# analog_in.net
KiCad netlist of a schematic drawn in Altium Designer
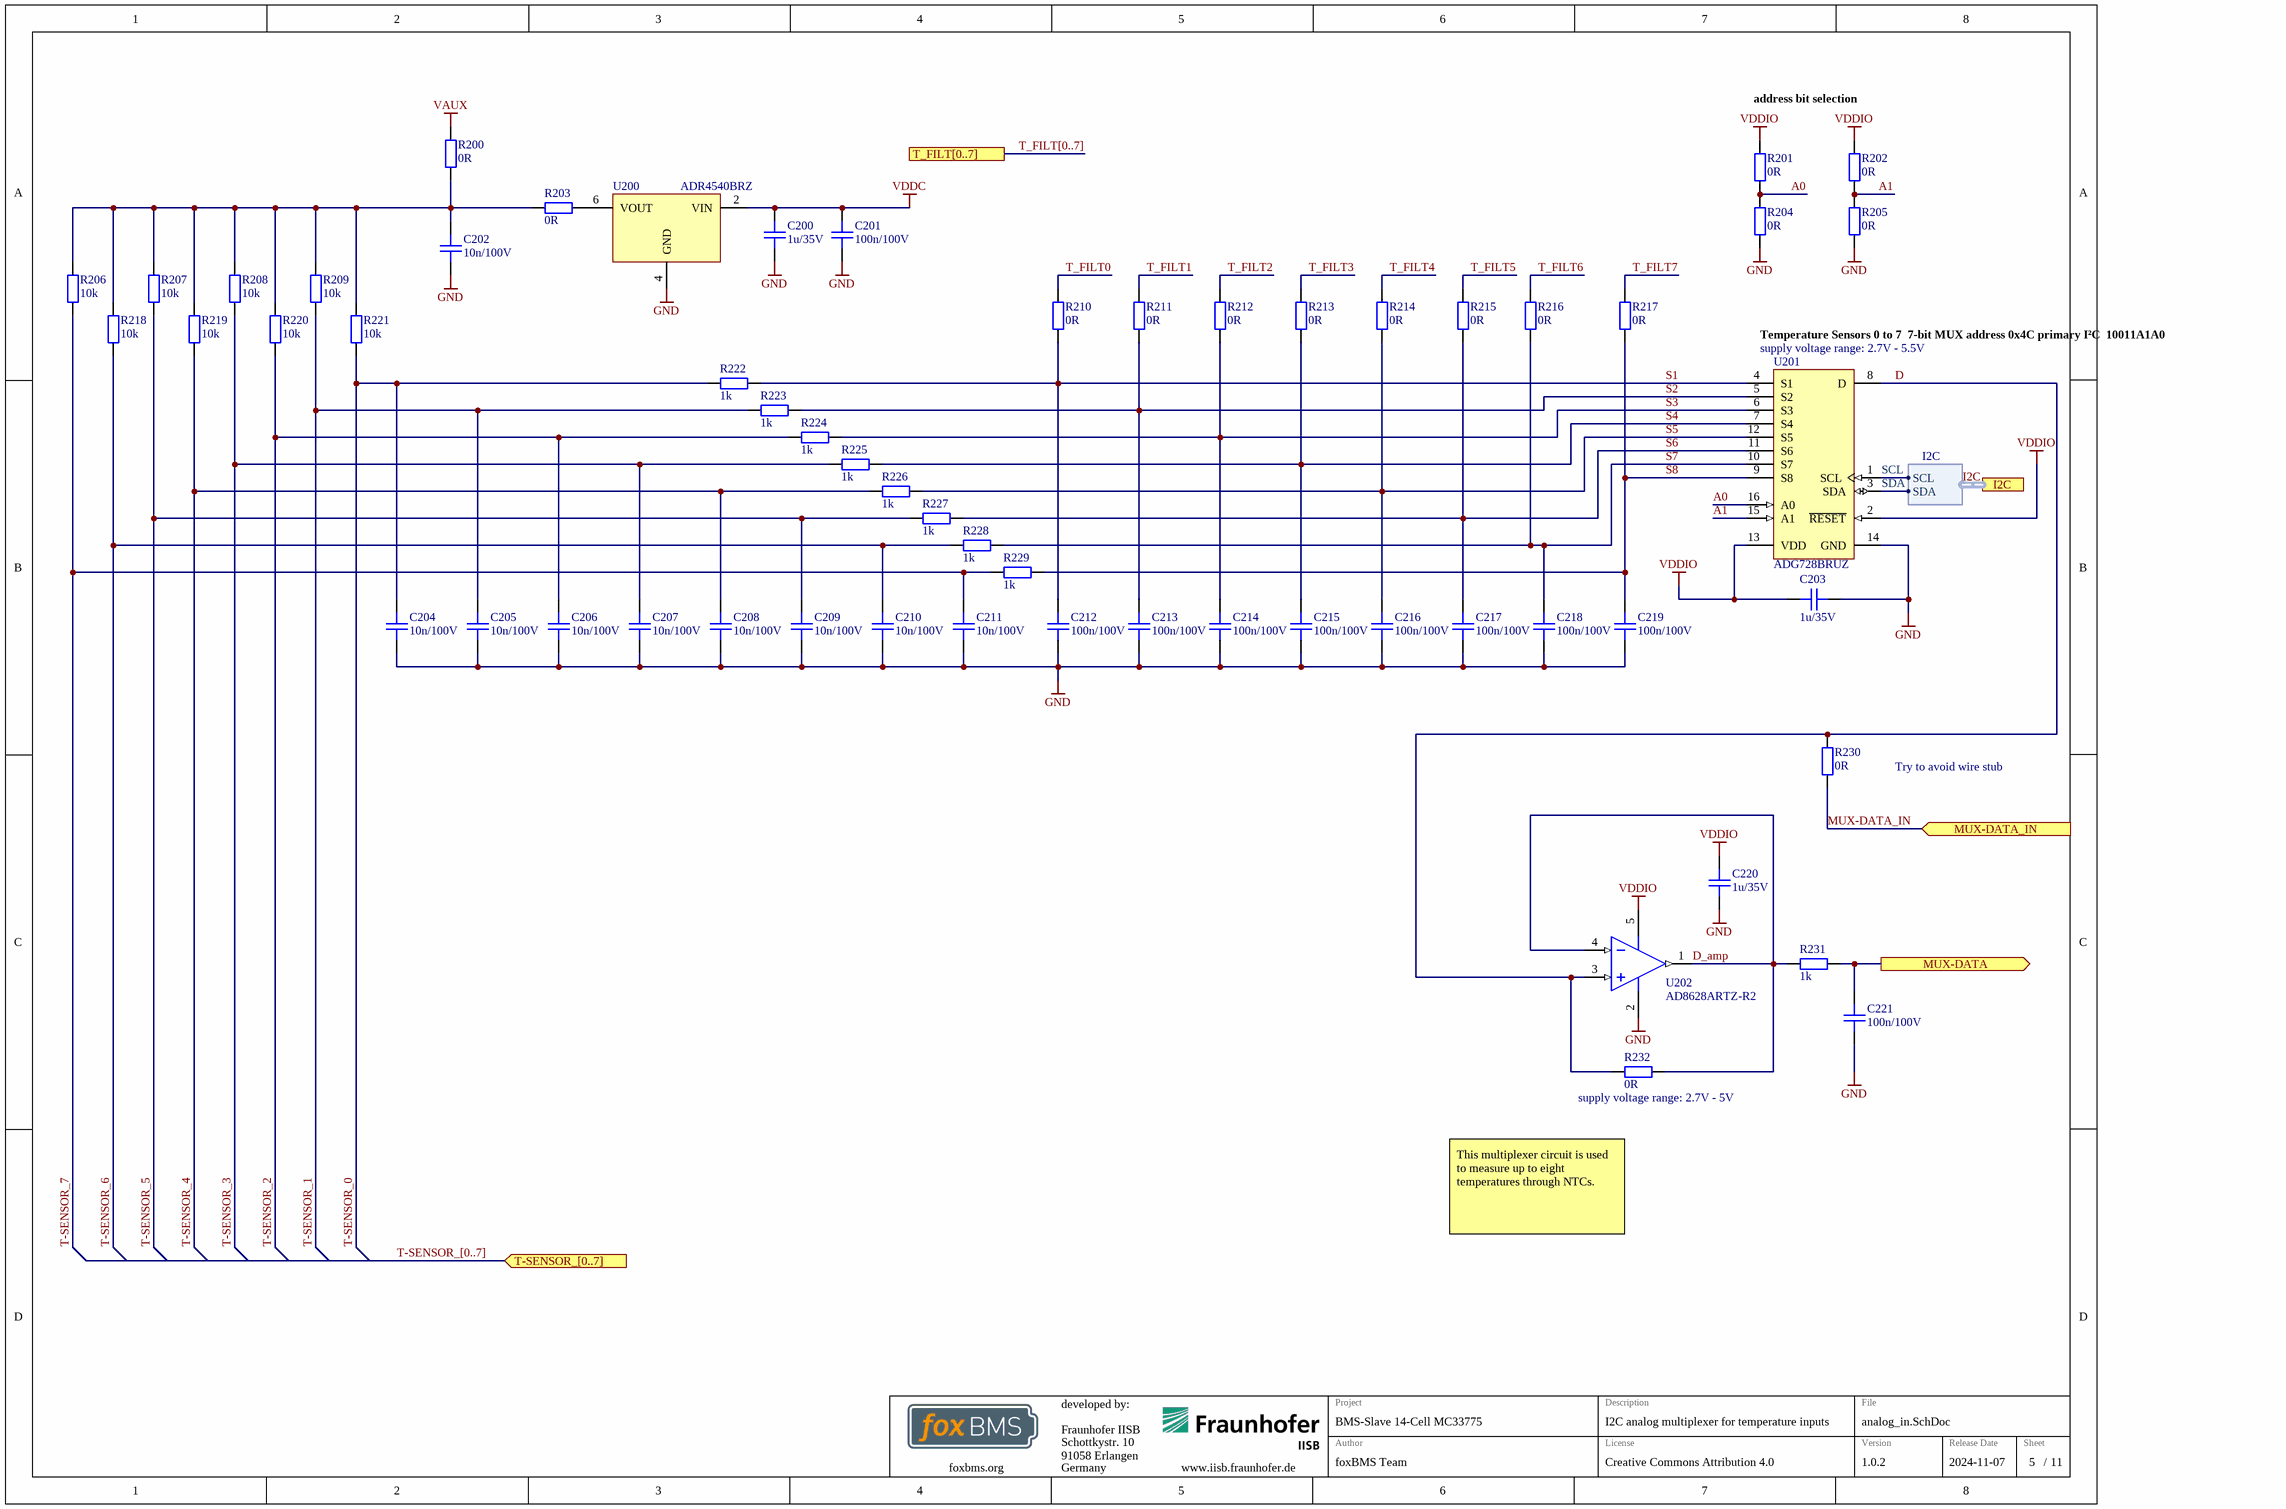
[diagram p0: analog_in.SchDoc]

(export (version "E")
  (design (tool "Eeschema 10.0.6"))
  (components
    (comp (ref "C200")
      (value "1u/35V")
      (footprint "CAPC1608X08N")
      (description "MLCC")
      (fields (field (name "PART NUMBER") "gen_C_ceramic_1u_35V_X7R_0603"))
      (libsource (lib "OE750") (part "C"))
    )
    (comp (ref "C201")
      (value "100n/100V")
      (footprint "CAPC1608X08N")
      (description "MLCC")
      (fields (field (name "PART NUMBER") "gen_C_ceramic_100n_100V_X7R_0603"))
      (libsource (lib "OE750") (part "C"))
    )
    (comp (ref "C202")
      (value "10n/100V")
      (footprint "CAPC1608X08N")
      (description "MLCC")
      (fields (field (name "PART NUMBER") "gen_C_ceramic_10n_100V_X7R_0603"))
      (libsource (lib "OE750") (part "C"))
    )
    (comp (ref "C203")
      (value "1u/35V")
      (footprint "CAPC1608X08N")
      (description "MLCC")
      (fields (field (name "PART NUMBER") "gen_C_ceramic_1u_35V_X7R_0603"))
      (libsource (lib "OE750") (part "C"))
    )
    (comp (ref "C204")
      (value "10n/100V")
      (footprint "CAPC1608X08N")
      (description "MLCC")
      (fields (field (name "PART NUMBER") "gen_C_ceramic_10n_100V_X7R_0603"))
      (libsource (lib "OE750") (part "C"))
    )
    (comp (ref "C205")
      (value "10n/100V")
      (footprint "CAPC1608X08N")
      (description "MLCC")
      (fields (field (name "PART NUMBER") "gen_C_ceramic_10n_100V_X7R_0603"))
      (libsource (lib "OE750") (part "C"))
    )
    (comp (ref "C206")
      (value "10n/100V")
      (footprint "CAPC1608X08N")
      (description "MLCC")
      (fields (field (name "PART NUMBER") "gen_C_ceramic_10n_100V_X7R_0603"))
      (libsource (lib "OE750") (part "C"))
    )
    (comp (ref "C207")
      (value "10n/100V")
      (footprint "CAPC1608X08N")
      (description "MLCC")
      (fields (field (name "PART NUMBER") "gen_C_ceramic_10n_100V_X7R_0603"))
      (libsource (lib "OE750") (part "C"))
    )
    (comp (ref "C208")
      (value "10n/100V")
      (footprint "CAPC1608X08N")
      (description "MLCC")
      (fields (field (name "PART NUMBER") "gen_C_ceramic_10n_100V_X7R_0603"))
      (libsource (lib "OE750") (part "C"))
    )
    (comp (ref "C209")
      (value "10n/100V")
      (footprint "CAPC1608X08N")
      (description "MLCC")
      (fields (field (name "PART NUMBER") "gen_C_ceramic_10n_100V_X7R_0603"))
      (libsource (lib "OE750") (part "C"))
    )
    (comp (ref "C210")
      (value "10n/100V")
      (footprint "CAPC1608X08N")
      (description "MLCC")
      (fields (field (name "PART NUMBER") "gen_C_ceramic_10n_100V_X7R_0603"))
      (libsource (lib "OE750") (part "C"))
    )
    (comp (ref "C211")
      (value "10n/100V")
      (footprint "CAPC1608X08N")
      (description "MLCC")
      (fields (field (name "PART NUMBER") "gen_C_ceramic_10n_100V_X7R_0603"))
      (libsource (lib "OE750") (part "C"))
    )
    (comp (ref "C212")
      (value "100n/100V")
      (footprint "CAPC1608X08N")
      (description "MLCC")
      (fields (field (name "PART NUMBER") "gen_C_ceramic_100n_100V_X7R_0603"))
      (libsource (lib "OE750") (part "C"))
    )
    (comp (ref "C213")
      (value "100n/100V")
      (footprint "CAPC1608X08N")
      (description "MLCC")
      (fields (field (name "PART NUMBER") "gen_C_ceramic_100n_100V_X7R_0603"))
      (libsource (lib "OE750") (part "C"))
    )
    (comp (ref "C214")
      (value "100n/100V")
      (footprint "CAPC1608X08N")
      (description "MLCC")
      (fields (field (name "PART NUMBER") "gen_C_ceramic_100n_100V_X7R_0603"))
      (libsource (lib "OE750") (part "C"))
    )
    (comp (ref "C215")
      (value "100n/100V")
      (footprint "CAPC1608X08N")
      (description "MLCC")
      (fields (field (name "PART NUMBER") "gen_C_ceramic_100n_100V_X7R_0603"))
      (libsource (lib "OE750") (part "C"))
    )
    (comp (ref "C216")
      (value "100n/100V")
      (footprint "CAPC1608X08N")
      (description "MLCC")
      (fields (field (name "PART NUMBER") "gen_C_ceramic_100n_100V_X7R_0603"))
      (libsource (lib "OE750") (part "C"))
    )
    (comp (ref "C217")
      (value "100n/100V")
      (footprint "CAPC1608X08N")
      (description "MLCC")
      (fields (field (name "PART NUMBER") "gen_C_ceramic_100n_100V_X7R_0603"))
      (libsource (lib "OE750") (part "C"))
    )
    (comp (ref "C218")
      (value "100n/100V")
      (footprint "CAPC1608X08N")
      (description "MLCC")
      (fields (field (name "PART NUMBER") "gen_C_ceramic_100n_100V_X7R_0603"))
      (libsource (lib "OE750") (part "C"))
    )
    (comp (ref "C219")
      (value "100n/100V")
      (footprint "CAPC1608X08N")
      (description "MLCC")
      (fields (field (name "PART NUMBER") "gen_C_ceramic_100n_100V_X7R_0603"))
      (libsource (lib "OE750") (part "C"))
    )
    (comp (ref "C220")
      (value "1u/35V")
      (footprint "CAPC1608X08N")
      (description "MLCC")
      (fields (field (name "PART NUMBER") "gen_C_ceramic_1u_35V_X7R_0603"))
      (libsource (lib "OE750") (part "C"))
    )
    (comp (ref "C221")
      (value "100n/100V")
      (footprint "CAPC1608X08N")
      (description "MLCC")
      (fields (field (name "PART NUMBER") "gen_C_ceramic_100n_100V_X7R_0603"))
      (libsource (lib "OE750") (part "C"))
    )
    (comp (ref "R200")
      (value "0R")
      (footprint "RESC1608X05N")
      (description "SMD Resistor 0R 0603")
      (fields (field (name "PART NUMBER") "gen_R_0R_0603") (field (name "POWER") "0.1W"))
      (libsource (lib "OE750") (part "R"))
    )
    (comp (ref "R201")
      (value "0R")
      (footprint "RESC1608X05N")
      (description "SMD Resistor 0R 0603")
      (fields (field (name "PART NUMBER") "gen_R_0R_0603") (field (name "POWER") "0.1W"))
      (libsource (lib "OE750") (part "R"))
    )
    (comp (ref "R202")
      (value "0R")
      (footprint "RESC1608X05N")
      (description "SMD Resistor 0R 0603")
      (fields (field (name "PART NUMBER") "gen_R_0R_0603") (field (name "POWER") "0.1W"))
      (libsource (lib "OE750") (part "R"))
    )
    (comp (ref "R203")
      (value "0R")
      (footprint "RESC1608X05N")
      (description "SMD Resistor 0R 0603")
      (fields (field (name "PART NUMBER") "gen_R_0R_0603") (field (name "POWER") "0.1W"))
      (libsource (lib "OE750") (part "R"))
    )
    (comp (ref "R204")
      (value "0R")
      (footprint "RESC1608X05N")
      (description "SMD Resistor 0R 0603")
      (fields (field (name "PART NUMBER") "gen_R_0R_0603") (field (name "POWER") "0.1W"))
      (libsource (lib "OE750") (part "R"))
    )
    (comp (ref "R205")
      (value "0R")
      (footprint "RESC1608X05N")
      (description "SMD Resistor 0R 0603")
      (fields (field (name "PART NUMBER") "gen_R_0R_0603") (field (name "POWER") "0.1W"))
      (libsource (lib "OE750") (part "R"))
    )
    (comp (ref "R206")
      (value "10k")
      (footprint "RESC1608X05N")
      (description "SMD Resistor 10k 0603")
      (fields (field (name "PART NUMBER") "gen_R_10k_0603") (field (name "TOLERANCE") "1%"))
      (libsource (lib "OE750") (part "R"))
    )
    (comp (ref "R207")
      (value "10k")
      (footprint "RESC1608X05N")
      (description "SMD Resistor 10k 0603")
      (fields (field (name "PART NUMBER") "gen_R_10k_0603") (field (name "TOLERANCE") "1%"))
      (libsource (lib "OE750") (part "R"))
    )
    (comp (ref "R208")
      (value "10k")
      (footprint "RESC1608X05N")
      (description "SMD Resistor 10k 0603")
      (fields (field (name "PART NUMBER") "gen_R_10k_0603") (field (name "TOLERANCE") "1%"))
      (libsource (lib "OE750") (part "R"))
    )
    (comp (ref "R209")
      (value "10k")
      (footprint "RESC1608X05N")
      (description "SMD Resistor 10k 0603")
      (fields (field (name "PART NUMBER") "gen_R_10k_0603") (field (name "TOLERANCE") "1%"))
      (libsource (lib "OE750") (part "R"))
    )
    (comp (ref "R210")
      (value "0R")
      (footprint "RESC1608X05N")
      (description "SMD Resistor 0R 0603")
      (fields (field (name "PART NUMBER") "gen_R_0R_0603") (field (name "POWER") "0.1W"))
      (libsource (lib "OE750") (part "R"))
    )
    (comp (ref "R211")
      (value "0R")
      (footprint "RESC1608X05N")
      (description "SMD Resistor 0R 0603")
      (fields (field (name "PART NUMBER") "gen_R_0R_0603") (field (name "POWER") "0.1W"))
      (libsource (lib "OE750") (part "R"))
    )
    (comp (ref "R212")
      (value "0R")
      (footprint "RESC1608X05N")
      (description "SMD Resistor 0R 0603")
      (fields (field (name "PART NUMBER") "gen_R_0R_0603") (field (name "POWER") "0.1W"))
      (libsource (lib "OE750") (part "R"))
    )
    (comp (ref "R213")
      (value "0R")
      (footprint "RESC1608X05N")
      (description "SMD Resistor 0R 0603")
      (fields (field (name "PART NUMBER") "gen_R_0R_0603") (field (name "POWER") "0.1W"))
      (libsource (lib "OE750") (part "R"))
    )
    (comp (ref "R214")
      (value "0R")
      (footprint "RESC1608X05N")
      (description "SMD Resistor 0R 0603")
      (fields (field (name "PART NUMBER") "gen_R_0R_0603") (field (name "POWER") "0.1W"))
      (libsource (lib "OE750") (part "R"))
    )
    (comp (ref "R215")
      (value "0R")
      (footprint "RESC1608X05N")
      (description "SMD Resistor 0R 0603")
      (fields (field (name "PART NUMBER") "gen_R_0R_0603") (field (name "POWER") "0.1W"))
      (libsource (lib "OE750") (part "R"))
    )
    (comp (ref "R216")
      (value "0R")
      (footprint "RESC1608X05N")
      (description "SMD Resistor 0R 0603")
      (fields (field (name "PART NUMBER") "gen_R_0R_0603") (field (name "POWER") "0.1W"))
      (libsource (lib "OE750") (part "R"))
    )
    (comp (ref "R217")
      (value "0R")
      (footprint "RESC1608X05N")
      (description "SMD Resistor 0R 0603")
      (fields (field (name "PART NUMBER") "gen_R_0R_0603") (field (name "POWER") "0.1W"))
      (libsource (lib "OE750") (part "R"))
    )
    (comp (ref "R218")
      (value "10k")
      (footprint "RESC1608X05N")
      (description "SMD Resistor 10k 0603")
      (fields (field (name "PART NUMBER") "gen_R_10k_0603") (field (name "TOLERANCE") "1%"))
      (libsource (lib "OE750") (part "R"))
    )
    (comp (ref "R219")
      (value "10k")
      (footprint "RESC1608X05N")
      (description "SMD Resistor 10k 0603")
      (fields (field (name "PART NUMBER") "gen_R_10k_0603") (field (name "TOLERANCE") "1%"))
      (libsource (lib "OE750") (part "R"))
    )
    (comp (ref "R220")
      (value "10k")
      (footprint "RESC1608X05N")
      (description "SMD Resistor 10k 0603")
      (fields (field (name "PART NUMBER") "gen_R_10k_0603") (field (name "TOLERANCE") "1%"))
      (libsource (lib "OE750") (part "R"))
    )
    (comp (ref "R221")
      (value "10k")
      (footprint "RESC1608X05N")
      (description "SMD Resistor 10k 0603")
      (fields (field (name "PART NUMBER") "gen_R_10k_0603") (field (name "TOLERANCE") "1%"))
      (libsource (lib "OE750") (part "R"))
    )
    (comp (ref "R222")
      (value "1k")
      (footprint "RESC1608X05N")
      (description "SMD Resistor 1k 0603")
      (fields (field (name "PART NUMBER") "gen_R_1k_0603") (field (name "TOLERANCE") "1%"))
      (libsource (lib "OE750") (part "R"))
    )
    (comp (ref "R223")
      (value "1k")
      (footprint "RESC1608X05N")
      (description "SMD Resistor 1k 0603")
      (fields (field (name "PART NUMBER") "gen_R_1k_0603") (field (name "TOLERANCE") "1%"))
      (libsource (lib "OE750") (part "R"))
    )
    (comp (ref "R224")
      (value "1k")
      (footprint "RESC1608X05N")
      (description "SMD Resistor 1k 0603")
      (fields (field (name "PART NUMBER") "gen_R_1k_0603") (field (name "TOLERANCE") "1%"))
      (libsource (lib "OE750") (part "R"))
    )
    (comp (ref "R225")
      (value "1k")
      (footprint "RESC1608X05N")
      (description "SMD Resistor 1k 0603")
      (fields (field (name "PART NUMBER") "gen_R_1k_0603") (field (name "TOLERANCE") "1%"))
      (libsource (lib "OE750") (part "R"))
    )
    (comp (ref "R226")
      (value "1k")
      (footprint "RESC1608X05N")
      (description "SMD Resistor 1k 0603")
      (fields (field (name "PART NUMBER") "gen_R_1k_0603") (field (name "TOLERANCE") "1%"))
      (libsource (lib "OE750") (part "R"))
    )
    (comp (ref "R227")
      (value "1k")
      (footprint "RESC1608X05N")
      (description "SMD Resistor 1k 0603")
      (fields (field (name "PART NUMBER") "gen_R_1k_0603") (field (name "TOLERANCE") "1%"))
      (libsource (lib "OE750") (part "R"))
    )
    (comp (ref "R228")
      (value "1k")
      (footprint "RESC1608X05N")
      (description "SMD Resistor 1k 0603")
      (fields (field (name "PART NUMBER") "gen_R_1k_0603") (field (name "TOLERANCE") "1%"))
      (libsource (lib "OE750") (part "R"))
    )
    (comp (ref "R229")
      (value "1k")
      (footprint "RESC1608X05N")
      (description "SMD Resistor 1k 0603")
      (fields (field (name "PART NUMBER") "gen_R_1k_0603") (field (name "TOLERANCE") "1%"))
      (libsource (lib "OE750") (part "R"))
    )
    (comp (ref "R230")
      (value "0R")
      (footprint "RESC1608X05N")
      (description "SMD Resistor 0R 0603")
      (fields (field (name "PART NUMBER") "gen_R_0R_0603") (field (name "POWER") "0.1W"))
      (libsource (lib "OE750") (part "R"))
    )
    (comp (ref "R231")
      (value "1k")
      (footprint "RESC1608X05N")
      (description "SMD Resistor 1k 0603")
      (fields (field (name "PART NUMBER") "gen_R_1k_0603") (field (name "TOLERANCE") "1%"))
      (libsource (lib "OE750") (part "R"))
    )
    (comp (ref "R232")
      (value "0R")
      (footprint "RESC1608X05N")
      (description "SMD Resistor 0R 0603")
      (fields (field (name "PART NUMBER") "gen_R_0R_0603") (field (name "POWER") "0.1W"))
      (libsource (lib "OE750") (part "R"))
    )
    (comp (ref "U200")
      (value "ADR4540BRZ")
      (footprint "SOIC127P600X175-8N")
      (description "Ultralow Noise, High Accuracy 4.096V Reference")
      (fields (field (name "MANUFACTURER") "Analog Devices"))
      (libsource (lib "OE750") (part "ADR45xx"))
    )
    (comp (ref "U201")
      (value "ADG728BRUZ")
      (footprint "ADI-RU-16_M")
      (fields (field (name "MANUFACTURER") "Analog Devices"))
      (libsource (lib "Altium Content Vault") (part "ADI-ADG728-RU-16"))
    )
    (comp (ref "U202")
      (value "AD8628ARTZ-R2")
      (footprint "ADI-RJ-5_M")
      (fields (field (name "MANUFACTURER") "Analog Devices") (field (name "GENERIC PART NUMBER") "AD8628"))
      (libsource (lib "Altium Content Vault") (part "ADI-ADxxxx-X-5"))
    )
  )
  (nets
    (net (code "2") (name "/A0") (class "Default")
      (node (ref "R201") (pin "1") (pinfunction "1_1") (pintype "passive"))
      (node (ref "R204") (pin "2") (pinfunction "2_2") (pintype "passive"))
      (node (ref "U201") (pin "16") (pinfunction "A0_16") (pintype "input"))
    )
    (net (code "3") (name "/A1") (class "Default")
      (node (ref "R202") (pin "1") (pinfunction "1_1") (pintype "passive"))
      (node (ref "R205") (pin "2") (pinfunction "2_2") (pintype "passive"))
      (node (ref "U201") (pin "15") (pinfunction "A1_15") (pintype "input"))
    )
    (net (code "4") (name "/D") (class "Default")
      (node (ref "R230") (pin "1") (pinfunction "1_1") (pintype "passive"))
      (node (ref "R232") (pin "1") (pinfunction "1_1") (pintype "passive"))
      (node (ref "U201") (pin "8") (pinfunction "D_8") (pintype "passive"))
      (node (ref "U202") (pin "3") (pinfunction "+IN_3") (pintype "input"))
    )
    (net (code "5") (name "/D_amp") (class "Default")
      (node (ref "R231") (pin "1") (pinfunction "1_1") (pintype "passive"))
      (node (ref "R232") (pin "2") (pinfunction "2_2") (pintype "passive"))
      (node (ref "U202") (pin "1") (pinfunction "OUT_1") (pintype "output"))
      (node (ref "U202") (pin "4") (pinfunction "-IN_4") (pintype "input"))
    )
    (net (code "7") (name "/MUX-DATA") (class "Default")
      (node (ref "C221") (pin "2") (pinfunction "2_2") (pintype "passive"))
      (node (ref "R231") (pin "2") (pinfunction "2_2") (pintype "passive"))
    )
    (net (code "8") (name "/MUX-DATA_IN") (class "Default")
      (node (ref "R230") (pin "2") (pinfunction "2_2") (pintype "passive"))
    )
    (net (code "9") (name "/S1") (class "Default")
      (node (ref "C212") (pin "2") (pinfunction "2_2") (pintype "passive"))
      (node (ref "R210") (pin "1") (pinfunction "1_1") (pintype "passive"))
      (node (ref "R222") (pin "1") (pinfunction "1_1") (pintype "passive"))
      (node (ref "U201") (pin "4") (pinfunction "S1_4") (pintype "passive"))
    )
    (net (code "10") (name "/S2") (class "Default")
      (node (ref "C213") (pin "2") (pinfunction "2_2") (pintype "passive"))
      (node (ref "R211") (pin "1") (pinfunction "1_1") (pintype "passive"))
      (node (ref "R223") (pin "1") (pinfunction "1_1") (pintype "passive"))
      (node (ref "U201") (pin "5") (pinfunction "S2_5") (pintype "passive"))
    )
    (net (code "11") (name "/S3") (class "Default")
      (node (ref "C214") (pin "2") (pinfunction "2_2") (pintype "passive"))
      (node (ref "R212") (pin "1") (pinfunction "1_1") (pintype "passive"))
      (node (ref "R224") (pin "1") (pinfunction "1_1") (pintype "passive"))
      (node (ref "U201") (pin "6") (pinfunction "S3_6") (pintype "passive"))
    )
    (net (code "12") (name "/S4") (class "Default")
      (node (ref "C215") (pin "2") (pinfunction "2_2") (pintype "passive"))
      (node (ref "R213") (pin "1") (pinfunction "1_1") (pintype "passive"))
      (node (ref "R225") (pin "1") (pinfunction "1_1") (pintype "passive"))
      (node (ref "U201") (pin "7") (pinfunction "S4_7") (pintype "passive"))
    )
    (net (code "13") (name "/S5") (class "Default")
      (node (ref "C216") (pin "2") (pinfunction "2_2") (pintype "passive"))
      (node (ref "R214") (pin "1") (pinfunction "1_1") (pintype "passive"))
      (node (ref "R226") (pin "1") (pinfunction "1_1") (pintype "passive"))
      (node (ref "U201") (pin "12") (pinfunction "S5_12") (pintype "passive"))
    )
    (net (code "14") (name "/S6") (class "Default")
      (node (ref "C217") (pin "2") (pinfunction "2_2") (pintype "passive"))
      (node (ref "R215") (pin "1") (pinfunction "1_1") (pintype "passive"))
      (node (ref "R227") (pin "1") (pinfunction "1_1") (pintype "passive"))
      (node (ref "U201") (pin "11") (pinfunction "S6_11") (pintype "passive"))
    )
    (net (code "15") (name "/S7") (class "Default")
      (node (ref "C218") (pin "2") (pinfunction "2_2") (pintype "passive"))
      (node (ref "R216") (pin "1") (pinfunction "1_1") (pintype "passive"))
      (node (ref "R228") (pin "1") (pinfunction "1_1") (pintype "passive"))
      (node (ref "U201") (pin "10") (pinfunction "S7_10") (pintype "passive"))
    )
    (net (code "16") (name "/S8") (class "Default")
      (node (ref "C219") (pin "2") (pinfunction "2_2") (pintype "passive"))
      (node (ref "R217") (pin "1") (pinfunction "1_1") (pintype "passive"))
      (node (ref "R229") (pin "1") (pinfunction "1_1") (pintype "passive"))
      (node (ref "U201") (pin "9") (pinfunction "S8_9") (pintype "passive"))
    )
    (net (code "17") (name "/SCL") (class "Default")
      (node (ref "U201") (pin "1") (pinfunction "SCL_1") (pintype "input"))
    )
    (net (code "18") (name "/SDA") (class "Default")
      (node (ref "U201") (pin "3") (pinfunction "SDA_3") (pintype "bidirectional"))
    )
    (net (code "19") (name "/T-SENSOR_0") (class "Default")
      (node (ref "C204") (pin "2") (pinfunction "2_2") (pintype "passive"))
      (node (ref "R221") (pin "1") (pinfunction "1_1") (pintype "passive"))
      (node (ref "R222") (pin "2") (pinfunction "2_2") (pintype "passive"))
    )
    (net (code "20") (name "/T-SENSOR_1") (class "Default")
      (node (ref "C205") (pin "2") (pinfunction "2_2") (pintype "passive"))
      (node (ref "R209") (pin "1") (pinfunction "1_1") (pintype "passive"))
      (node (ref "R223") (pin "2") (pinfunction "2_2") (pintype "passive"))
    )
    (net (code "21") (name "/T-SENSOR_2") (class "Default")
      (node (ref "C206") (pin "2") (pinfunction "2_2") (pintype "passive"))
      (node (ref "R220") (pin "1") (pinfunction "1_1") (pintype "passive"))
      (node (ref "R224") (pin "2") (pinfunction "2_2") (pintype "passive"))
    )
    (net (code "22") (name "/T-SENSOR_3") (class "Default")
      (node (ref "C207") (pin "2") (pinfunction "2_2") (pintype "passive"))
      (node (ref "R208") (pin "1") (pinfunction "1_1") (pintype "passive"))
      (node (ref "R225") (pin "2") (pinfunction "2_2") (pintype "passive"))
    )
    (net (code "23") (name "/T-SENSOR_4") (class "Default")
      (node (ref "C208") (pin "2") (pinfunction "2_2") (pintype "passive"))
      (node (ref "R219") (pin "1") (pinfunction "1_1") (pintype "passive"))
      (node (ref "R226") (pin "2") (pinfunction "2_2") (pintype "passive"))
    )
    (net (code "24") (name "/T-SENSOR_5") (class "Default")
      (node (ref "C209") (pin "2") (pinfunction "2_2") (pintype "passive"))
      (node (ref "R207") (pin "1") (pinfunction "1_1") (pintype "passive"))
      (node (ref "R227") (pin "2") (pinfunction "2_2") (pintype "passive"))
    )
    (net (code "25") (name "/T-SENSOR_6") (class "Default")
      (node (ref "C210") (pin "2") (pinfunction "2_2") (pintype "passive"))
      (node (ref "R218") (pin "1") (pinfunction "1_1") (pintype "passive"))
      (node (ref "R228") (pin "2") (pinfunction "2_2") (pintype "passive"))
    )
    (net (code "26") (name "/T-SENSOR_7") (class "Default")
      (node (ref "C211") (pin "2") (pinfunction "2_2") (pintype "passive"))
      (node (ref "R206") (pin "1") (pinfunction "1_1") (pintype "passive"))
      (node (ref "R229") (pin "2") (pinfunction "2_2") (pintype "passive"))
    )
    (net (code "28") (name "/T_FILT0") (class "Default")
      (node (ref "R210") (pin "2") (pinfunction "2_2") (pintype "passive"))
    )
    (net (code "29") (name "/T_FILT1") (class "Default")
      (node (ref "R211") (pin "2") (pinfunction "2_2") (pintype "passive"))
    )
    (net (code "30") (name "/T_FILT2") (class "Default")
      (node (ref "R212") (pin "2") (pinfunction "2_2") (pintype "passive"))
    )
    (net (code "31") (name "/T_FILT3") (class "Default")
      (node (ref "R213") (pin "2") (pinfunction "2_2") (pintype "passive"))
    )
    (net (code "32") (name "/T_FILT4") (class "Default")
      (node (ref "R214") (pin "2") (pinfunction "2_2") (pintype "passive"))
    )
    (net (code "33") (name "/T_FILT5") (class "Default")
      (node (ref "R215") (pin "2") (pinfunction "2_2") (pintype "passive"))
    )
    (net (code "34") (name "/T_FILT6") (class "Default")
      (node (ref "R216") (pin "2") (pinfunction "2_2") (pintype "passive"))
    )
    (net (code "35") (name "/T_FILT7") (class "Default")
      (node (ref "R217") (pin "2") (pinfunction "2_2") (pintype "passive"))
    )
    (net (code "37") (name "GND") (class "Default")
      (node (ref "C200") (pin "1") (pinfunction "1_1") (pintype "passive"))
      (node (ref "C201") (pin "1") (pinfunction "1_1") (pintype "passive"))
      (node (ref "C202") (pin "1") (pinfunction "1_1") (pintype "passive"))
      (node (ref "C203") (pin "1") (pinfunction "1_1") (pintype "passive"))
      (node (ref "C204") (pin "1") (pinfunction "1_1") (pintype "passive"))
      (node (ref "C205") (pin "1") (pinfunction "1_1") (pintype "passive"))
      (node (ref "C206") (pin "1") (pinfunction "1_1") (pintype "passive"))
      (node (ref "C207") (pin "1") (pinfunction "1_1") (pintype "passive"))
      (node (ref "C208") (pin "1") (pinfunction "1_1") (pintype "passive"))
      (node (ref "C209") (pin "1") (pinfunction "1_1") (pintype "passive"))
      (node (ref "C210") (pin "1") (pinfunction "1_1") (pintype "passive"))
      (node (ref "C211") (pin "1") (pinfunction "1_1") (pintype "passive"))
      (node (ref "C212") (pin "1") (pinfunction "1_1") (pintype "passive"))
      (node (ref "C213") (pin "1") (pinfunction "1_1") (pintype "passive"))
      (node (ref "C214") (pin "1") (pinfunction "1_1") (pintype "passive"))
      (node (ref "C215") (pin "1") (pinfunction "1_1") (pintype "passive"))
      (node (ref "C216") (pin "1") (pinfunction "1_1") (pintype "passive"))
      (node (ref "C217") (pin "1") (pinfunction "1_1") (pintype "passive"))
      (node (ref "C218") (pin "1") (pinfunction "1_1") (pintype "passive"))
      (node (ref "C219") (pin "1") (pinfunction "1_1") (pintype "passive"))
      (node (ref "C220") (pin "1") (pinfunction "1_1") (pintype "passive"))
      (node (ref "C221") (pin "1") (pinfunction "1_1") (pintype "passive"))
      (node (ref "R204") (pin "1") (pinfunction "1_1") (pintype "passive"))
      (node (ref "R205") (pin "1") (pinfunction "1_1") (pintype "passive"))
      (node (ref "U200") (pin "4") (pinfunction "GND_4") (pintype "power_in"))
      (node (ref "U201") (pin "14") (pinfunction "GND_14") (pintype "power_in"))
      (node (ref "U202") (pin "2") (pinfunction "-V_2") (pintype "power_in"))
    )
    (net (code "38") (name "Net-(C202-Pad2)") (class "Default")
      (node (ref "C202") (pin "2") (pinfunction "2_2") (pintype "passive"))
      (node (ref "R200") (pin "1") (pinfunction "1_1") (pintype "passive"))
      (node (ref "R203") (pin "1") (pinfunction "1_1") (pintype "passive"))
      (node (ref "R206") (pin "2") (pinfunction "2_2") (pintype "passive"))
      (node (ref "R207") (pin "2") (pinfunction "2_2") (pintype "passive"))
      (node (ref "R208") (pin "2") (pinfunction "2_2") (pintype "passive"))
      (node (ref "R209") (pin "2") (pinfunction "2_2") (pintype "passive"))
      (node (ref "R218") (pin "2") (pinfunction "2_2") (pintype "passive"))
      (node (ref "R219") (pin "2") (pinfunction "2_2") (pintype "passive"))
      (node (ref "R220") (pin "2") (pinfunction "2_2") (pintype "passive"))
      (node (ref "R221") (pin "2") (pinfunction "2_2") (pintype "passive"))
    )
    (net (code "39") (name "Net-(U200-VOUT)") (class "Default")
      (node (ref "R203") (pin "2") (pinfunction "2_2") (pintype "passive"))
      (node (ref "U200") (pin "6") (pinfunction "VOUT_6") (pintype "power_in"))
    )
    (net (code "40") (name "VAUX") (class "Default")
      (node (ref "R200") (pin "2") (pinfunction "2_2") (pintype "passive"))
    )
    (net (code "41") (name "VDDC") (class "Default")
      (node (ref "C200") (pin "2") (pinfunction "2_2") (pintype "passive"))
      (node (ref "C201") (pin "2") (pinfunction "2_2") (pintype "passive"))
      (node (ref "U200") (pin "2") (pinfunction "VIN_2") (pintype "power_in"))
    )
    (net (code "42") (name "VDDIO") (class "Default")
      (node (ref "C203") (pin "2") (pinfunction "2_2") (pintype "passive"))
      (node (ref "C220") (pin "2") (pinfunction "2_2") (pintype "passive"))
      (node (ref "R201") (pin "2") (pinfunction "2_2") (pintype "passive"))
      (node (ref "R202") (pin "2") (pinfunction "2_2") (pintype "passive"))
      (node (ref "U201") (pin "13") (pinfunction "VDD_13") (pintype "power_in"))
      (node (ref "U201") (pin "2") (pinfunction "~{RESET}_2") (pintype "input"))
      (node (ref "U202") (pin "5") (pinfunction "+V_5") (pintype "power_in"))
    )
  )
)
